# E6_Esp32_TS26C01_v3.net
KiCad netlist of a schematic drawn in EAGLE
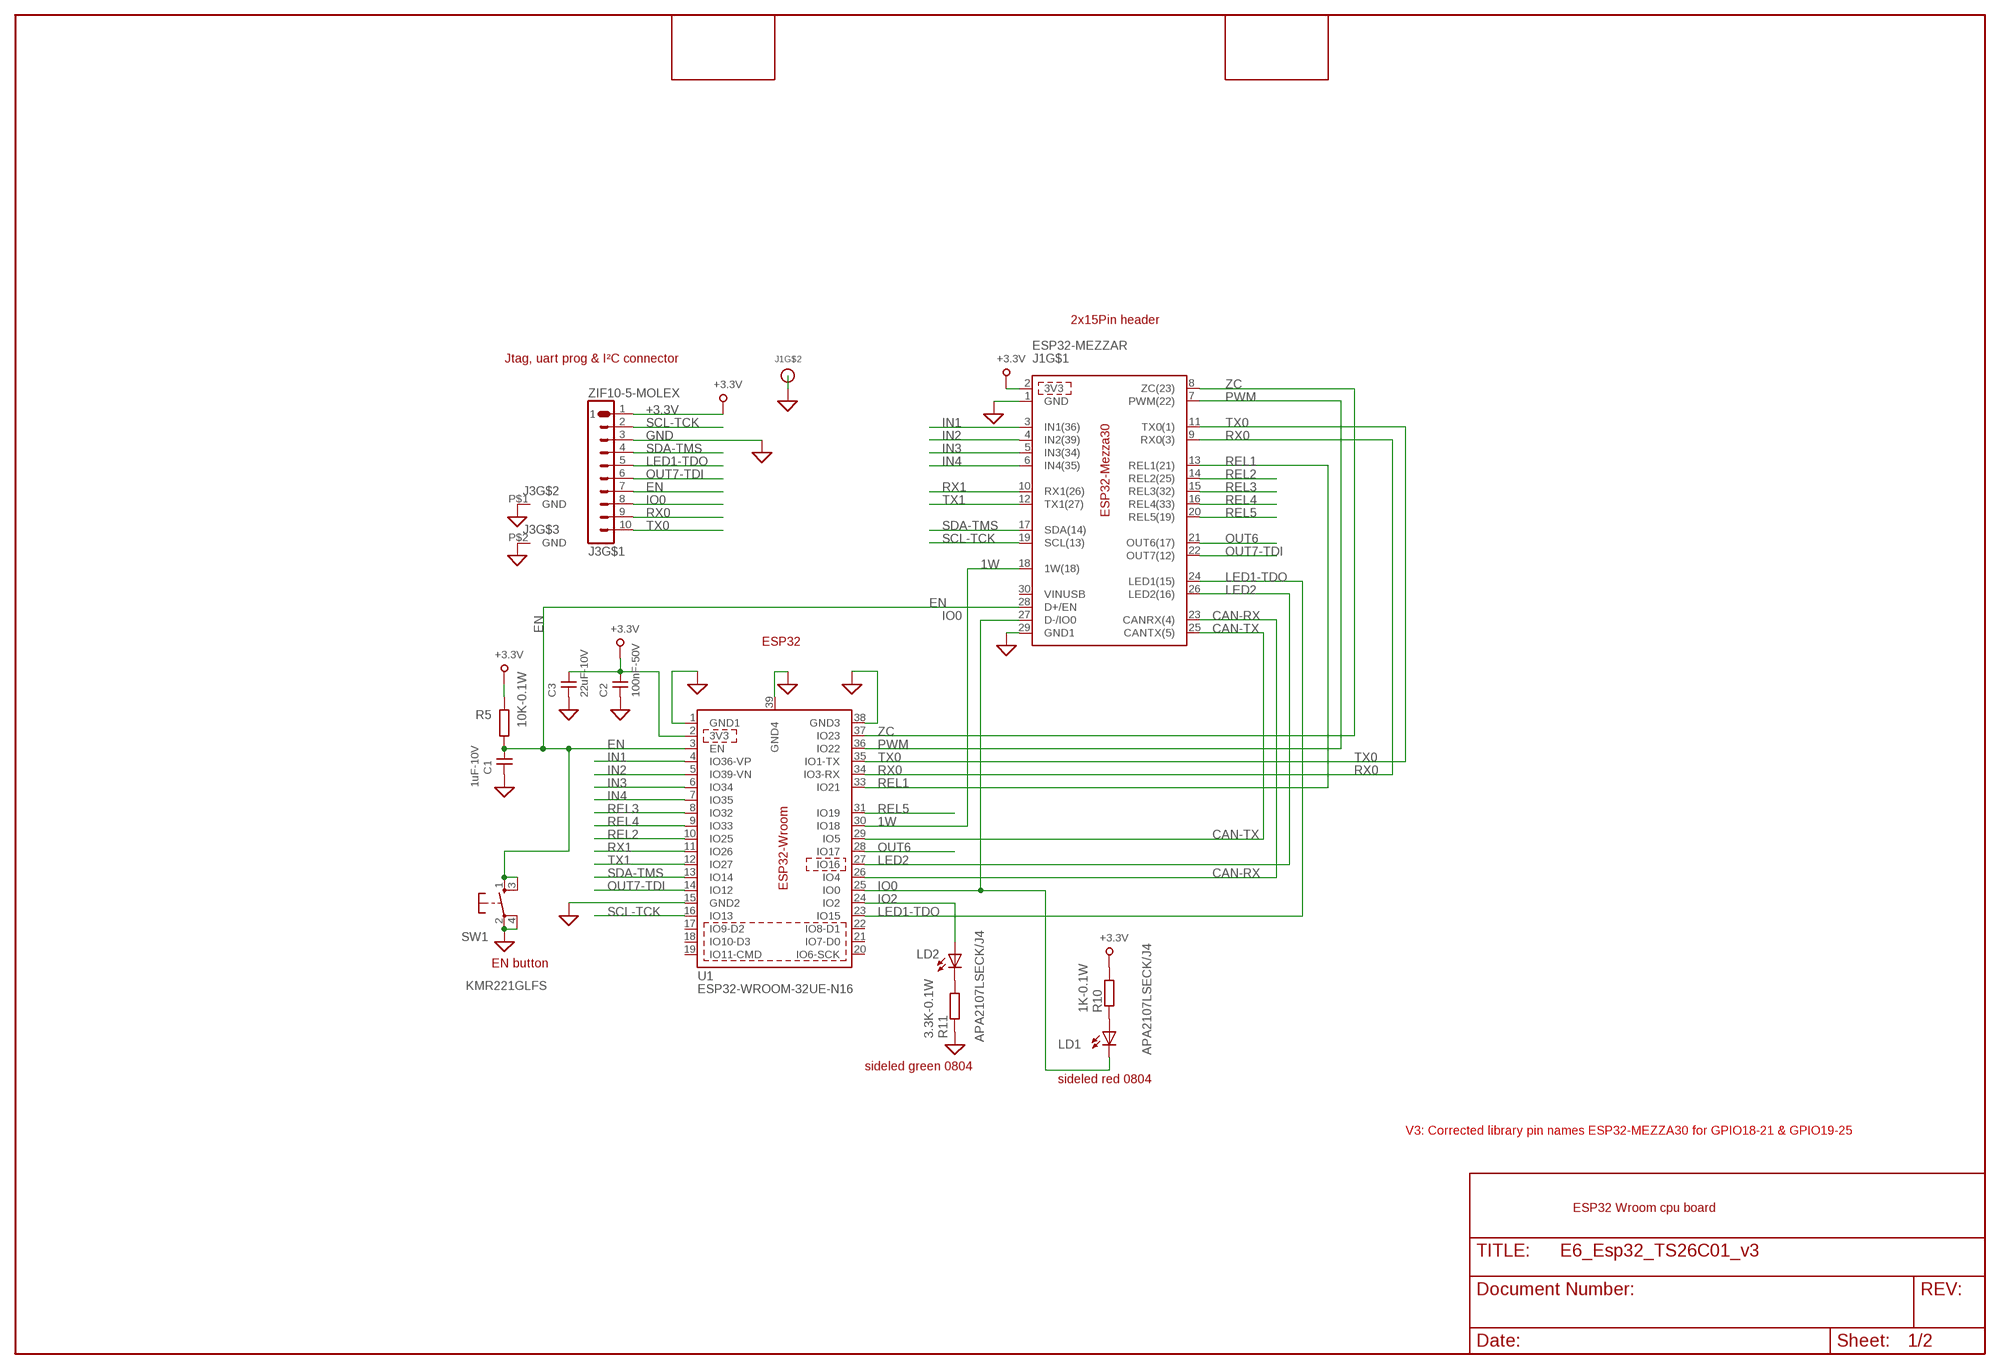
[diagram p0: schematic, sheet 1]
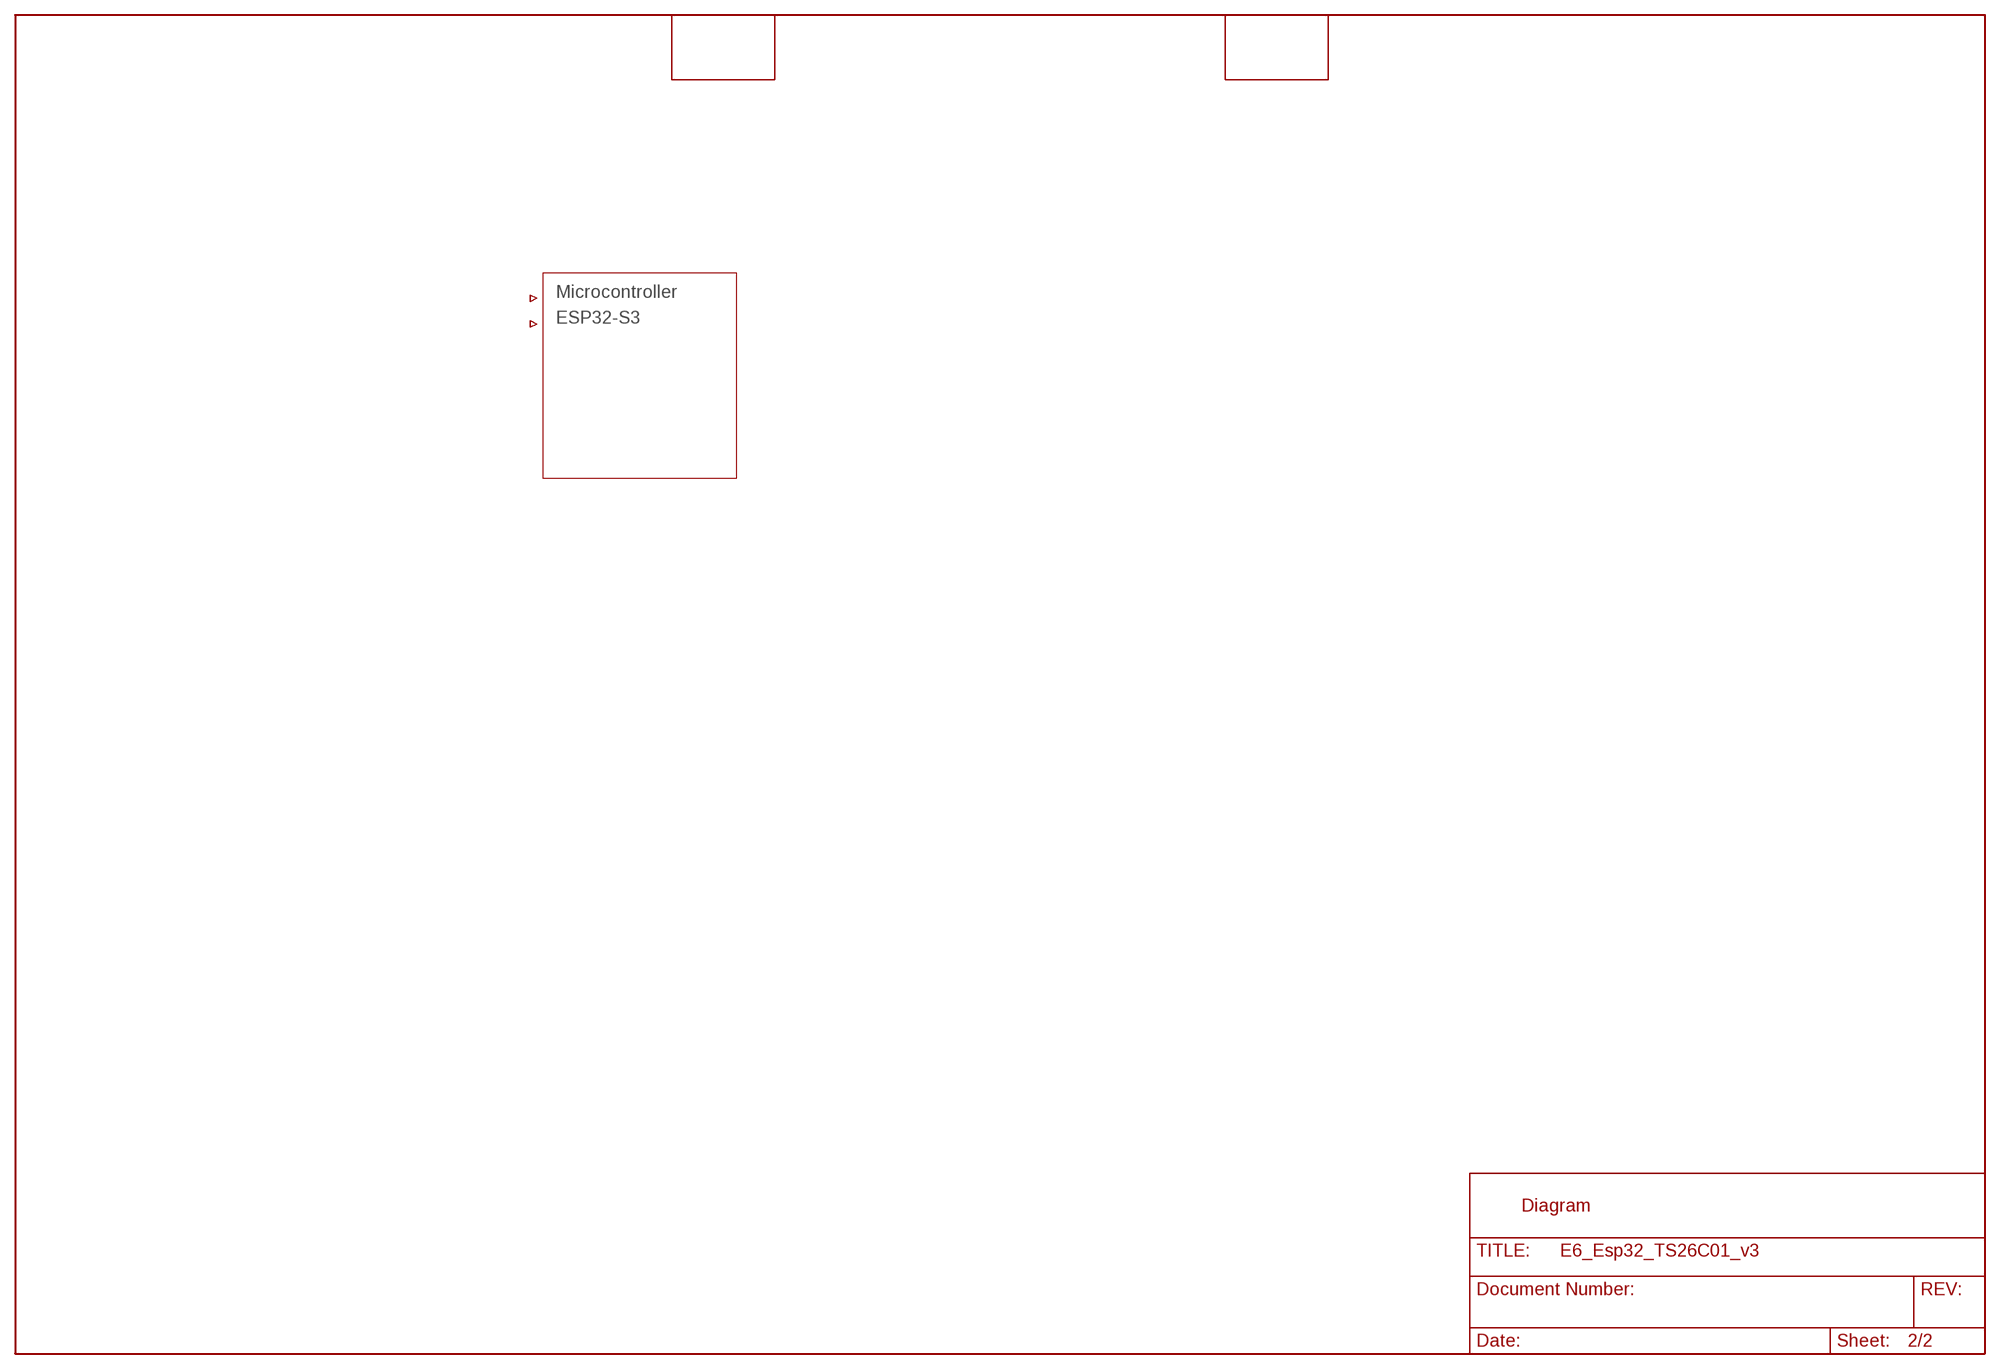
[diagram p1: schematic, sheet 2]

(export (version "E")
  (design (tool "Eeschema 10.0.6"))
  (components
    (comp (ref "C1")
      (value "1uF-10V")
      (footprint "eagle-import:C0603")
      (libsource (lib "eagle-import") (part "CAP-0603-L"))
    )
    (comp (ref "C2")
      (value "100nF-50V")
      (footprint "eagle-import:C0603")
      (libsource (lib "eagle-import") (part "CAP-0603-L"))
    )
    (comp (ref "C3")
      (value "22uF-10V")
      (footprint "eagle-import:C0603")
      (libsource (lib "eagle-import") (part "CAP-0603-L"))
    )
    (comp (ref "J1")
      (value "ESP32-MEZZAR")
      (footprint "eagle-import:ESP32-MEZZA25-R")
      (libsource (lib "eagle-import") (part "ESP32-MEZZAR"))
    )
    (comp (ref "J3")
      (value "ZIF10-5-MOLEX")
      (footprint "eagle-import:52746-1071-J")
      (libsource (lib "eagle-import") (part "ZIF10-5-MOLEXSTD"))
    )
    (comp (ref "LD1")
      (value "APA2107LSECK/J4")
      (footprint "eagle-import:SIDELED_0805")
      (libsource (lib "eagle-import") (part "SIDELED_0805"))
    )
    (comp (ref "LD2")
      (value "APA2107LSECK/J4")
      (footprint "eagle-import:SIDELED_0805")
      (libsource (lib "eagle-import") (part "SIDELED_0805"))
    )
    (comp (ref "R5")
      (value "10K-0.1W")
      (footprint "eagle-import:0603")
      (libsource (lib "eagle-import") (part "R-EU_R0603-S"))
    )
    (comp (ref "R10")
      (value "1K-0.1W")
      (footprint "eagle-import:0603")
      (libsource (lib "eagle-import") (part "R-EU_R0603-S"))
    )
    (comp (ref "R11")
      (value "3.3K-0.1W")
      (footprint "eagle-import:0603")
      (libsource (lib "eagle-import") (part "R-EU_R0603-S"))
    )
    (comp (ref "SW1")
      (value "KMR221GLFS")
      (footprint "eagle-import:SW-KMS-HOLE-NOGND")
      (libsource (lib "eagle-import") (part "SW-TACT-NOGNDSIDE"))
    )
    (comp (ref "U1")
      (value "ESP32-WROOM-32UE-N16")
      (footprint "eagle-import:ESP32-WROOM-32UE")
      (libsource (lib "eagle-import") (part "ESP32-WROOM-UE"))
    )
  )
  (nets
    (net (code "1") (name "+3.3V") (class "Default")
      (node (ref "C2") (pin "2") (pinfunction "2_2") (pintype "passive"))
      (node (ref "C3") (pin "2") (pinfunction "2_2") (pintype "passive"))
      (node (ref "J1") (pin "2") (pinfunction "3V3_2") (pintype "bidirectional"))
      (node (ref "J3") (pin "1") (pinfunction "1_1") (pintype "passive"))
      (node (ref "R10") (pin "1") (pinfunction "1_1") (pintype "passive"))
      (node (ref "R5") (pin "1") (pinfunction "1_1") (pintype "passive"))
      (node (ref "U1") (pin "2") (pinfunction "3V3_2") (pintype "power_in"))
    )
    (net (code "2") (name "1W") (class "Default")
      (node (ref "J1") (pin "18") (pinfunction "1W(18)_18") (pintype "bidirectional"))
      (node (ref "U1") (pin "30") (pinfunction "IO18_30") (pintype "bidirectional"))
    )
    (net (code "3") (name "CAN-RX") (class "Default")
      (node (ref "J1") (pin "23") (pinfunction "CANRX(4)_23") (pintype "bidirectional"))
      (node (ref "U1") (pin "26") (pinfunction "IO4_26") (pintype "bidirectional"))
    )
    (net (code "4") (name "CAN-TX") (class "Default")
      (node (ref "J1") (pin "25") (pinfunction "CANTX(5)_25") (pintype "bidirectional"))
      (node (ref "U1") (pin "29") (pinfunction "IO5_29") (pintype "bidirectional"))
    )
    (net (code "5") (name "EN") (class "Default")
      (node (ref "C1") (pin "2") (pinfunction "2_2") (pintype "passive"))
      (node (ref "J1") (pin "28") (pinfunction "D+/EN_28") (pintype "bidirectional"))
      (node (ref "J3") (pin "7") (pinfunction "7_7") (pintype "passive"))
      (node (ref "R5") (pin "2") (pinfunction "2_2") (pintype "passive"))
      (node (ref "SW1") (pin "1") (pinfunction "S_1") (pintype "passive"))
      (node (ref "SW1") (pin "3") (pinfunction "S_3") (pintype "passive"))
      (node (ref "U1") (pin "3") (pinfunction "EN_3") (pintype "bidirectional"))
    )
    (net (code "6") (name "GND") (class "Default")
      (node (ref "C1") (pin "1") (pinfunction "1_1") (pintype "passive"))
      (node (ref "C2") (pin "1") (pinfunction "1_1") (pintype "passive"))
      (node (ref "C3") (pin "1") (pinfunction "1_1") (pintype "passive"))
      (node (ref "J1") (pin "1") (pinfunction "GND_1") (pintype "power_in"))
      (node (ref "J1") (pin "29") (pinfunction "GND1_29") (pintype "power_in"))
      (node (ref "J1") (pin "31") (pinfunction "P$1_31") (pintype "passive"))
      (node (ref "J3") (pin "3") (pinfunction "3_3") (pintype "passive"))
      (node (ref "J3") (pin "P$1") (pinfunction "GND_P$1") (pintype "power_in"))
      (node (ref "J3") (pin "P$2") (pinfunction "GND_P$2") (pintype "power_in"))
      (node (ref "R11") (pin "2") (pinfunction "2_2") (pintype "passive"))
      (node (ref "SW1") (pin "2") (pinfunction "P_2") (pintype "passive"))
      (node (ref "SW1") (pin "4") (pinfunction "P_4") (pintype "passive"))
      (node (ref "U1") (pin "1") (pinfunction "GND1_1") (pintype "power_in"))
      (node (ref "U1") (pin "15") (pinfunction "GND2_15") (pintype "power_in"))
      (node (ref "U1") (pin "38") (pinfunction "GND3_38") (pintype "power_in"))
      (node (ref "U1") (pin "39") (pinfunction "GND4_39") (pintype "power_in"))
    )
    (net (code "7") (name "IN1") (class "Default")
      (node (ref "J1") (pin "3") (pinfunction "IN1(36)_3") (pintype "bidirectional"))
      (node (ref "U1") (pin "4") (pinfunction "IO36-VP_4") (pintype "bidirectional"))
    )
    (net (code "8") (name "IN2") (class "Default")
      (node (ref "J1") (pin "4") (pinfunction "IN2(39)_4") (pintype "bidirectional"))
      (node (ref "U1") (pin "5") (pinfunction "IO39-VN_5") (pintype "bidirectional"))
    )
    (net (code "9") (name "IN3") (class "Default")
      (node (ref "J1") (pin "5") (pinfunction "IN3(34)_5") (pintype "bidirectional"))
      (node (ref "U1") (pin "6") (pinfunction "IO34_6") (pintype "bidirectional"))
    )
    (net (code "10") (name "IN4") (class "Default")
      (node (ref "J1") (pin "6") (pinfunction "IN4(35)_6") (pintype "bidirectional"))
      (node (ref "U1") (pin "7") (pinfunction "IO35_7") (pintype "bidirectional"))
    )
    (net (code "11") (name "IO0") (class "Default")
      (node (ref "J1") (pin "27") (pinfunction "D-/IO0_27") (pintype "bidirectional"))
      (node (ref "J3") (pin "8") (pinfunction "8_8") (pintype "passive"))
      (node (ref "LD1") (pin "C") (pinfunction "C_C") (pintype "passive"))
      (node (ref "U1") (pin "25") (pinfunction "IO0_25") (pintype "bidirectional"))
    )
    (net (code "12") (name "IO2") (class "Default")
      (node (ref "LD2") (pin "A") (pinfunction "A_A") (pintype "passive"))
      (node (ref "U1") (pin "24") (pinfunction "IO2_24") (pintype "bidirectional"))
    )
    (net (code "13") (name "LED1-TDO") (class "Default")
      (node (ref "J1") (pin "24") (pinfunction "LED1(15)_24") (pintype "bidirectional"))
      (node (ref "J3") (pin "5") (pinfunction "5_5") (pintype "passive"))
      (node (ref "U1") (pin "23") (pinfunction "IO15_23") (pintype "bidirectional"))
    )
    (net (code "14") (name "LED2") (class "Default")
      (node (ref "J1") (pin "26") (pinfunction "LED2(16)_26") (pintype "bidirectional"))
      (node (ref "U1") (pin "27") (pinfunction "IO16_27") (pintype "bidirectional"))
    )
    (net (code "15") (name "Net-(LD1-PadA)") (class "Default")
      (node (ref "LD1") (pin "A") (pinfunction "A_A") (pintype "passive"))
      (node (ref "R10") (pin "2") (pinfunction "2_2") (pintype "passive"))
    )
    (net (code "16") (name "Net-(LD2-PadC)") (class "Default")
      (node (ref "LD2") (pin "C") (pinfunction "C_C") (pintype "passive"))
      (node (ref "R11") (pin "1") (pinfunction "1_1") (pintype "passive"))
    )
    (net (code "17") (name "OUT6") (class "Default")
      (node (ref "J1") (pin "21") (pinfunction "OUT6(17)_21") (pintype "bidirectional"))
      (node (ref "U1") (pin "28") (pinfunction "IO17_28") (pintype "bidirectional"))
    )
    (net (code "18") (name "OUT7-TDI") (class "Default")
      (node (ref "J1") (pin "22") (pinfunction "OUT7(12)_22") (pintype "bidirectional"))
      (node (ref "J3") (pin "6") (pinfunction "6_6") (pintype "passive"))
      (node (ref "U1") (pin "14") (pinfunction "IO12_14") (pintype "bidirectional"))
    )
    (net (code "19") (name "PWM") (class "Default")
      (node (ref "J1") (pin "7") (pinfunction "PWM(22)_7") (pintype "bidirectional"))
      (node (ref "U1") (pin "36") (pinfunction "IO22_36") (pintype "bidirectional"))
    )
    (net (code "20") (name "REL1") (class "Default")
      (node (ref "J1") (pin "13") (pinfunction "REL1(21)_13") (pintype "bidirectional"))
      (node (ref "U1") (pin "33") (pinfunction "IO21_33") (pintype "bidirectional"))
    )
    (net (code "21") (name "REL2") (class "Default")
      (node (ref "J1") (pin "14") (pinfunction "REL2(25)_14") (pintype "bidirectional"))
      (node (ref "U1") (pin "10") (pinfunction "IO25_10") (pintype "bidirectional"))
    )
    (net (code "22") (name "REL3") (class "Default")
      (node (ref "J1") (pin "15") (pinfunction "REL3(32)_15") (pintype "bidirectional"))
      (node (ref "U1") (pin "8") (pinfunction "IO32_8") (pintype "bidirectional"))
    )
    (net (code "23") (name "REL4") (class "Default")
      (node (ref "J1") (pin "16") (pinfunction "REL4(33)_16") (pintype "bidirectional"))
      (node (ref "U1") (pin "9") (pinfunction "IO33_9") (pintype "bidirectional"))
    )
    (net (code "24") (name "REL5") (class "Default")
      (node (ref "J1") (pin "20") (pinfunction "REL5(19)_20") (pintype "bidirectional"))
      (node (ref "U1") (pin "31") (pinfunction "IO19_31") (pintype "bidirectional"))
    )
    (net (code "25") (name "RX0") (class "Default")
      (node (ref "J1") (pin "9") (pinfunction "RX0(3)_9") (pintype "bidirectional"))
      (node (ref "J3") (pin "9") (pinfunction "9_9") (pintype "passive"))
      (node (ref "U1") (pin "34") (pinfunction "IO3-RX_34") (pintype "bidirectional"))
    )
    (net (code "26") (name "RX1") (class "Default")
      (node (ref "J1") (pin "10") (pinfunction "RX1(26)_10") (pintype "bidirectional"))
      (node (ref "U1") (pin "11") (pinfunction "IO26_11") (pintype "bidirectional"))
    )
    (net (code "27") (name "SCL-TCK") (class "Default")
      (node (ref "J1") (pin "19") (pinfunction "SCL(13)_19") (pintype "bidirectional"))
      (node (ref "J3") (pin "2") (pinfunction "2_2") (pintype "passive"))
      (node (ref "U1") (pin "16") (pinfunction "IO13_16") (pintype "bidirectional"))
    )
    (net (code "28") (name "SDA-TMS") (class "Default")
      (node (ref "J1") (pin "17") (pinfunction "SDA(14)_17") (pintype "bidirectional"))
      (node (ref "J3") (pin "4") (pinfunction "4_4") (pintype "passive"))
      (node (ref "U1") (pin "13") (pinfunction "IO14_13") (pintype "bidirectional"))
    )
    (net (code "29") (name "TX0") (class "Default")
      (node (ref "J1") (pin "11") (pinfunction "TX0(1)_11") (pintype "bidirectional"))
      (node (ref "J3") (pin "10") (pinfunction "10_10") (pintype "passive"))
      (node (ref "U1") (pin "35") (pinfunction "IO1-TX_35") (pintype "bidirectional"))
    )
    (net (code "30") (name "TX1") (class "Default")
      (node (ref "J1") (pin "12") (pinfunction "TX1(27)_12") (pintype "bidirectional"))
      (node (ref "U1") (pin "12") (pinfunction "IO27_12") (pintype "bidirectional"))
    )
    (net (code "31") (name "ZC") (class "Default")
      (node (ref "J1") (pin "8") (pinfunction "ZC(23)_8") (pintype "bidirectional"))
      (node (ref "U1") (pin "37") (pinfunction "IO23_37") (pintype "bidirectional"))
    )
    (net (code "32") (name "unconnected-(J1A-VINUSB-Pad30)") (class "Default")
      (node (ref "J1") (pin "30") (pinfunction "VINUSB_30") (pintype "bidirectional"))
    )
    (net (code "33") (name "unconnected-(U1-IO6-SCK-Pad20)") (class "Default")
      (node (ref "U1") (pin "20") (pinfunction "IO6-SCK_20") (pintype "no_connect"))
    )
    (net (code "34") (name "unconnected-(U1-IO7-D0-Pad21)") (class "Default")
      (node (ref "U1") (pin "21") (pinfunction "IO7-D0_21") (pintype "no_connect"))
    )
    (net (code "35") (name "unconnected-(U1-IO8-D1-Pad22)") (class "Default")
      (node (ref "U1") (pin "22") (pinfunction "IO8-D1_22") (pintype "no_connect"))
    )
    (net (code "36") (name "unconnected-(U1-IO9-D2-Pad17)") (class "Default")
      (node (ref "U1") (pin "17") (pinfunction "IO9-D2_17") (pintype "bidirectional"))
    )
    (net (code "37") (name "unconnected-(U1-IO10-D3-Pad18)") (class "Default")
      (node (ref "U1") (pin "18") (pinfunction "IO10-D3_18") (pintype "no_connect"))
    )
    (net (code "38") (name "unconnected-(U1-IO11-CMD-Pad19)") (class "Default")
      (node (ref "U1") (pin "19") (pinfunction "IO11-CMD_19") (pintype "no_connect"))
    )
  )
)
